# 2_classyTKL_matrix.net
KiCad netlist of a schematic drawn in Altium Designer
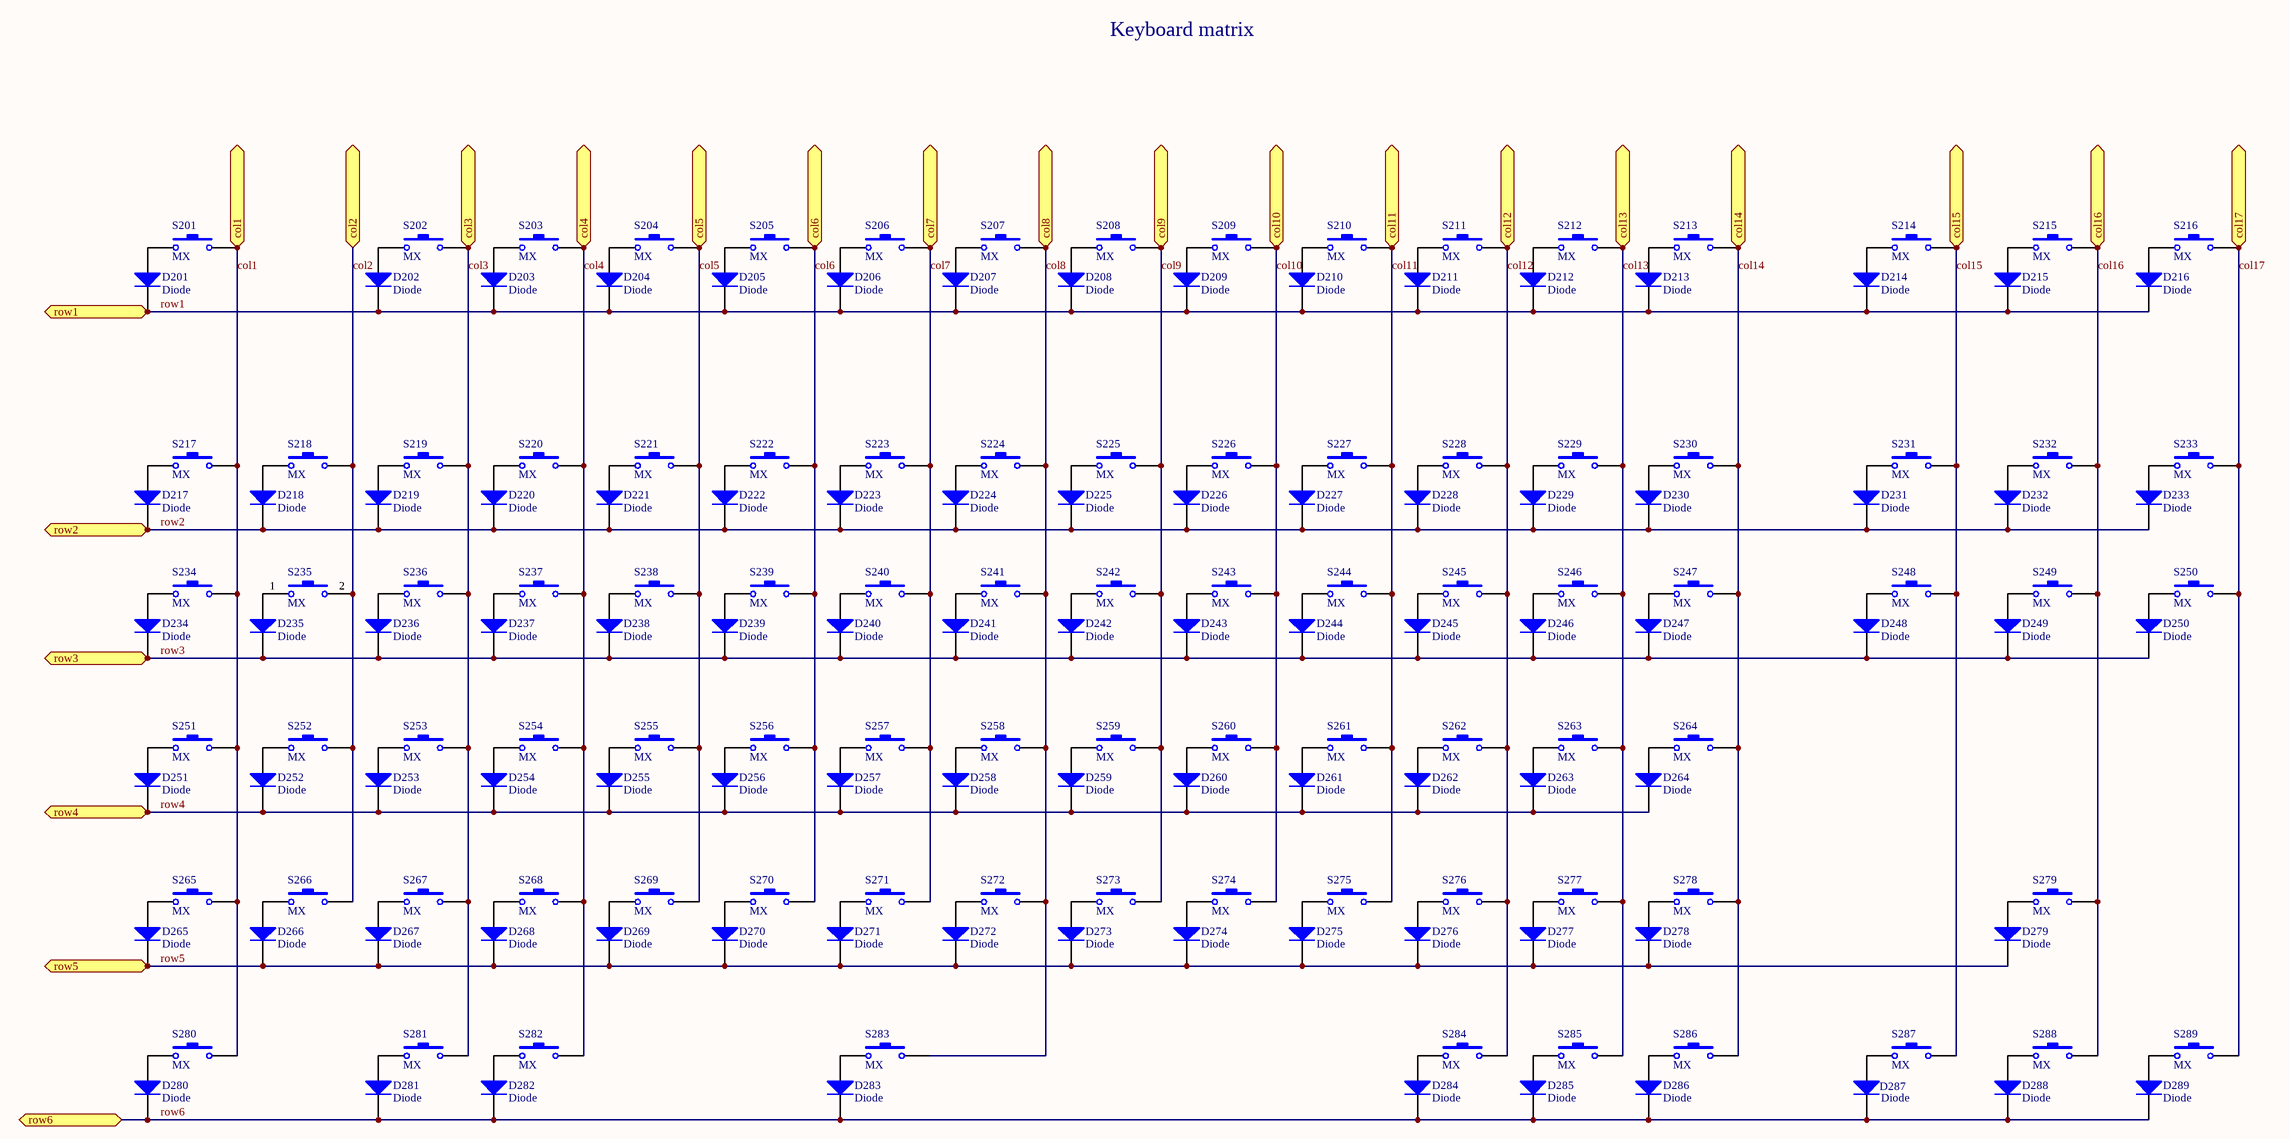
[diagram p0: 2_classyTKL_matrix.SchDoc]

(export (version "E")
  (design (tool "Eeschema 10.0.6"))
  (components
    (comp (ref "D201")
      (value "Diode")
      (footprint "D0603[1608]")
      (description "Default Diode")
      (fields (field (name "MFG") "Bourns Inc.") (field (name "LCSC PART #") "C109002"))
      (libsource (lib "Miscellaneous Devices") (part "Diode"))
    )
    (comp (ref "D202")
      (value "Diode")
      (footprint "D0603[1608]")
      (description "Default Diode")
      (fields (field (name "MFG") "Bourns Inc.") (field (name "LCSC PART #") "C109002"))
      (libsource (lib "Miscellaneous Devices") (part "Diode"))
    )
    (comp (ref "D203")
      (value "Diode")
      (footprint "D0603[1608]")
      (description "Default Diode")
      (fields (field (name "MFG") "Bourns Inc.") (field (name "LCSC PART #") "C109002"))
      (libsource (lib "Miscellaneous Devices") (part "Diode"))
    )
    (comp (ref "D204")
      (value "Diode")
      (footprint "D0603[1608]")
      (description "Default Diode")
      (fields (field (name "MFG") "Bourns Inc.") (field (name "LCSC PART #") "C109002"))
      (libsource (lib "Miscellaneous Devices") (part "Diode"))
    )
    (comp (ref "D205")
      (value "Diode")
      (footprint "D0603[1608]")
      (description "Default Diode")
      (fields (field (name "MFG") "Bourns Inc.") (field (name "LCSC PART #") "C109002"))
      (libsource (lib "Miscellaneous Devices") (part "Diode"))
    )
    (comp (ref "D206")
      (value "Diode")
      (footprint "D0603[1608]")
      (description "Default Diode")
      (fields (field (name "MFG") "Bourns Inc.") (field (name "LCSC PART #") "C109002"))
      (libsource (lib "Miscellaneous Devices") (part "Diode"))
    )
    (comp (ref "D207")
      (value "Diode")
      (footprint "D0603[1608]")
      (description "Default Diode")
      (fields (field (name "MFG") "Bourns Inc.") (field (name "LCSC PART #") "C109002"))
      (libsource (lib "Miscellaneous Devices") (part "Diode"))
    )
    (comp (ref "D208")
      (value "Diode")
      (footprint "D0603[1608]")
      (description "Default Diode")
      (fields (field (name "MFG") "Bourns Inc.") (field (name "LCSC PART #") "C109002"))
      (libsource (lib "Miscellaneous Devices") (part "Diode"))
    )
    (comp (ref "D209")
      (value "Diode")
      (footprint "D0603[1608]")
      (description "Default Diode")
      (fields (field (name "MFG") "Bourns Inc.") (field (name "LCSC PART #") "C109002"))
      (libsource (lib "Miscellaneous Devices") (part "Diode"))
    )
    (comp (ref "D210")
      (value "Diode")
      (footprint "D0603[1608]")
      (description "Default Diode")
      (fields (field (name "MFG") "Bourns Inc.") (field (name "LCSC PART #") "C109002"))
      (libsource (lib "Miscellaneous Devices") (part "Diode"))
    )
    (comp (ref "D211")
      (value "Diode")
      (footprint "D0603[1608]")
      (description "Default Diode")
      (fields (field (name "MFG") "Bourns Inc.") (field (name "LCSC PART #") "C109002"))
      (libsource (lib "Miscellaneous Devices") (part "Diode"))
    )
    (comp (ref "D212")
      (value "Diode")
      (footprint "D0603[1608]")
      (description "Default Diode")
      (fields (field (name "MFG") "Bourns Inc.") (field (name "LCSC PART #") "C109002"))
      (libsource (lib "Miscellaneous Devices") (part "Diode"))
    )
    (comp (ref "D213")
      (value "Diode")
      (footprint "D0603[1608]")
      (description "Default Diode")
      (fields (field (name "MFG") "Bourns Inc.") (field (name "LCSC PART #") "C109002"))
      (libsource (lib "Miscellaneous Devices") (part "Diode"))
    )
    (comp (ref "D214")
      (value "Diode")
      (footprint "D0603[1608]")
      (description "Default Diode")
      (fields (field (name "MFG") "Bourns Inc.") (field (name "LCSC PART #") "C109002"))
      (libsource (lib "Miscellaneous Devices") (part "Diode"))
    )
    (comp (ref "D215")
      (value "Diode")
      (footprint "D0603[1608]")
      (description "Default Diode")
      (fields (field (name "MFG") "Bourns Inc.") (field (name "LCSC PART #") "C109002"))
      (libsource (lib "Miscellaneous Devices") (part "Diode"))
    )
    (comp (ref "D216")
      (value "Diode")
      (footprint "D0603[1608]")
      (description "Default Diode")
      (fields (field (name "MFG") "Bourns Inc.") (field (name "LCSC PART #") "C109002"))
      (libsource (lib "Miscellaneous Devices") (part "Diode"))
    )
    (comp (ref "D217")
      (value "Diode")
      (footprint "D0603[1608]")
      (description "Default Diode")
      (fields (field (name "MFG") "Bourns Inc.") (field (name "LCSC PART #") "C109002"))
      (libsource (lib "Miscellaneous Devices") (part "Diode"))
    )
    (comp (ref "D218")
      (value "Diode")
      (footprint "D0603[1608]")
      (description "Default Diode")
      (fields (field (name "MFG") "Bourns Inc.") (field (name "LCSC PART #") "C109002"))
      (libsource (lib "Miscellaneous Devices") (part "Diode"))
    )
    (comp (ref "D219")
      (value "Diode")
      (footprint "D0603[1608]")
      (description "Default Diode")
      (fields (field (name "MFG") "Bourns Inc.") (field (name "LCSC PART #") "C109002"))
      (libsource (lib "Miscellaneous Devices") (part "Diode"))
    )
    (comp (ref "D220")
      (value "Diode")
      (footprint "D0603[1608]")
      (description "Default Diode")
      (fields (field (name "MFG") "Bourns Inc.") (field (name "LCSC PART #") "C109002"))
      (libsource (lib "Miscellaneous Devices") (part "Diode"))
    )
    (comp (ref "D221")
      (value "Diode")
      (footprint "D0603[1608]")
      (description "Default Diode")
      (fields (field (name "MFG") "Bourns Inc.") (field (name "LCSC PART #") "C109002"))
      (libsource (lib "Miscellaneous Devices") (part "Diode"))
    )
    (comp (ref "D222")
      (value "Diode")
      (footprint "D0603[1608]")
      (description "Default Diode")
      (fields (field (name "MFG") "Bourns Inc.") (field (name "LCSC PART #") "C109002"))
      (libsource (lib "Miscellaneous Devices") (part "Diode"))
    )
    (comp (ref "D223")
      (value "Diode")
      (footprint "D0603[1608]")
      (description "Default Diode")
      (fields (field (name "MFG") "Bourns Inc.") (field (name "LCSC PART #") "C109002"))
      (libsource (lib "Miscellaneous Devices") (part "Diode"))
    )
    (comp (ref "D224")
      (value "Diode")
      (footprint "D0603[1608]")
      (description "Default Diode")
      (fields (field (name "MFG") "Bourns Inc.") (field (name "LCSC PART #") "C109002"))
      (libsource (lib "Miscellaneous Devices") (part "Diode"))
    )
    (comp (ref "D225")
      (value "Diode")
      (footprint "D0603[1608]")
      (description "Default Diode")
      (fields (field (name "MFG") "Bourns Inc.") (field (name "LCSC PART #") "C109002"))
      (libsource (lib "Miscellaneous Devices") (part "Diode"))
    )
    (comp (ref "D226")
      (value "Diode")
      (footprint "D0603[1608]")
      (description "Default Diode")
      (fields (field (name "MFG") "Bourns Inc.") (field (name "LCSC PART #") "C109002"))
      (libsource (lib "Miscellaneous Devices") (part "Diode"))
    )
    (comp (ref "D227")
      (value "Diode")
      (footprint "D0603[1608]")
      (description "Default Diode")
      (fields (field (name "MFG") "Bourns Inc.") (field (name "LCSC PART #") "C109002"))
      (libsource (lib "Miscellaneous Devices") (part "Diode"))
    )
    (comp (ref "D228")
      (value "Diode")
      (footprint "D0603[1608]")
      (description "Default Diode")
      (fields (field (name "MFG") "Bourns Inc.") (field (name "LCSC PART #") "C109002"))
      (libsource (lib "Miscellaneous Devices") (part "Diode"))
    )
    (comp (ref "D229")
      (value "Diode")
      (footprint "D0603[1608]")
      (description "Default Diode")
      (fields (field (name "MFG") "Bourns Inc.") (field (name "LCSC PART #") "C109002"))
      (libsource (lib "Miscellaneous Devices") (part "Diode"))
    )
    (comp (ref "D230")
      (value "Diode")
      (footprint "D0603[1608]")
      (description "Default Diode")
      (fields (field (name "MFG") "Bourns Inc.") (field (name "LCSC PART #") "C109002"))
      (libsource (lib "Miscellaneous Devices") (part "Diode"))
    )
    (comp (ref "D231")
      (value "Diode")
      (footprint "D0603[1608]")
      (description "Default Diode")
      (fields (field (name "MFG") "Bourns Inc.") (field (name "LCSC PART #") "C109002"))
      (libsource (lib "Miscellaneous Devices") (part "Diode"))
    )
    (comp (ref "D232")
      (value "Diode")
      (footprint "D0603[1608]")
      (description "Default Diode")
      (fields (field (name "MFG") "Bourns Inc.") (field (name "LCSC PART #") "C109002"))
      (libsource (lib "Miscellaneous Devices") (part "Diode"))
    )
    (comp (ref "D233")
      (value "Diode")
      (footprint "D0603[1608]")
      (description "Default Diode")
      (fields (field (name "MFG") "Bourns Inc.") (field (name "LCSC PART #") "C109002"))
      (libsource (lib "Miscellaneous Devices") (part "Diode"))
    )
    (comp (ref "D234")
      (value "Diode")
      (footprint "D0603[1608]")
      (description "Default Diode")
      (fields (field (name "MFG") "Bourns Inc.") (field (name "LCSC PART #") "C109002"))
      (libsource (lib "Miscellaneous Devices") (part "Diode"))
    )
    (comp (ref "D235")
      (value "Diode")
      (footprint "D0603[1608]")
      (description "Default Diode")
      (fields (field (name "MFG") "Bourns Inc.") (field (name "LCSC PART #") "C109002"))
      (libsource (lib "Miscellaneous Devices") (part "Diode"))
    )
    (comp (ref "D236")
      (value "Diode")
      (footprint "D0603[1608]")
      (description "Default Diode")
      (fields (field (name "MFG") "Bourns Inc.") (field (name "LCSC PART #") "C109002"))
      (libsource (lib "Miscellaneous Devices") (part "Diode"))
    )
    (comp (ref "D237")
      (value "Diode")
      (footprint "D0603[1608]")
      (description "Default Diode")
      (fields (field (name "MFG") "Bourns Inc.") (field (name "LCSC PART #") "C109002"))
      (libsource (lib "Miscellaneous Devices") (part "Diode"))
    )
    (comp (ref "D238")
      (value "Diode")
      (footprint "D0603[1608]")
      (description "Default Diode")
      (fields (field (name "MFG") "Bourns Inc.") (field (name "LCSC PART #") "C109002"))
      (libsource (lib "Miscellaneous Devices") (part "Diode"))
    )
    (comp (ref "D239")
      (value "Diode")
      (footprint "D0603[1608]")
      (description "Default Diode")
      (fields (field (name "MFG") "Bourns Inc.") (field (name "LCSC PART #") "C109002"))
      (libsource (lib "Miscellaneous Devices") (part "Diode"))
    )
    (comp (ref "D240")
      (value "Diode")
      (footprint "D0603[1608]")
      (description "Default Diode")
      (fields (field (name "MFG") "Bourns Inc.") (field (name "LCSC PART #") "C109002"))
      (libsource (lib "Miscellaneous Devices") (part "Diode"))
    )
    (comp (ref "D241")
      (value "Diode")
      (footprint "D0603[1608]")
      (description "Default Diode")
      (fields (field (name "MFG") "Bourns Inc.") (field (name "LCSC PART #") "C109002"))
      (libsource (lib "Miscellaneous Devices") (part "Diode"))
    )
    (comp (ref "D242")
      (value "Diode")
      (footprint "D0603[1608]")
      (description "Default Diode")
      (fields (field (name "MFG") "Bourns Inc.") (field (name "LCSC PART #") "C109002"))
      (libsource (lib "Miscellaneous Devices") (part "Diode"))
    )
    (comp (ref "D243")
      (value "Diode")
      (footprint "D0603[1608]")
      (description "Default Diode")
      (fields (field (name "MFG") "Bourns Inc.") (field (name "LCSC PART #") "C109002"))
      (libsource (lib "Miscellaneous Devices") (part "Diode"))
    )
    (comp (ref "D244")
      (value "Diode")
      (footprint "D0603[1608]")
      (description "Default Diode")
      (fields (field (name "MFG") "Bourns Inc.") (field (name "LCSC PART #") "C109002"))
      (libsource (lib "Miscellaneous Devices") (part "Diode"))
    )
    (comp (ref "D245")
      (value "Diode")
      (footprint "D0603[1608]")
      (description "Default Diode")
      (fields (field (name "MFG") "Bourns Inc.") (field (name "LCSC PART #") "C109002"))
      (libsource (lib "Miscellaneous Devices") (part "Diode"))
    )
    (comp (ref "D246")
      (value "Diode")
      (footprint "D0603[1608]")
      (description "Default Diode")
      (fields (field (name "MFG") "Bourns Inc.") (field (name "LCSC PART #") "C109002"))
      (libsource (lib "Miscellaneous Devices") (part "Diode"))
    )
    (comp (ref "D247")
      (value "Diode")
      (footprint "D0603[1608]")
      (description "Default Diode")
      (fields (field (name "MFG") "Bourns Inc.") (field (name "LCSC PART #") "C109002"))
      (libsource (lib "Miscellaneous Devices") (part "Diode"))
    )
    (comp (ref "D248")
      (value "Diode")
      (footprint "D0603[1608]")
      (description "Default Diode")
      (fields (field (name "MFG") "Bourns Inc.") (field (name "LCSC PART #") "C109002"))
      (libsource (lib "Miscellaneous Devices") (part "Diode"))
    )
    (comp (ref "D249")
      (value "Diode")
      (footprint "D0603[1608]")
      (description "Default Diode")
      (fields (field (name "MFG") "Bourns Inc.") (field (name "LCSC PART #") "C109002"))
      (libsource (lib "Miscellaneous Devices") (part "Diode"))
    )
    (comp (ref "D250")
      (value "Diode")
      (footprint "D0603[1608]")
      (description "Default Diode")
      (fields (field (name "MFG") "Bourns Inc.") (field (name "LCSC PART #") "C109002"))
      (libsource (lib "Miscellaneous Devices") (part "Diode"))
    )
    (comp (ref "D251")
      (value "Diode")
      (footprint "D0603[1608]")
      (description "Default Diode")
      (fields (field (name "MFG") "Bourns Inc.") (field (name "LCSC PART #") "C109002"))
      (libsource (lib "Miscellaneous Devices") (part "Diode"))
    )
    (comp (ref "D252")
      (value "Diode")
      (footprint "D0603[1608]")
      (description "Default Diode")
      (fields (field (name "MFG") "Bourns Inc.") (field (name "LCSC PART #") "C109002"))
      (libsource (lib "Miscellaneous Devices") (part "Diode"))
    )
    (comp (ref "D253")
      (value "Diode")
      (footprint "D0603[1608]")
      (description "Default Diode")
      (fields (field (name "MFG") "Bourns Inc.") (field (name "LCSC PART #") "C109002"))
      (libsource (lib "Miscellaneous Devices") (part "Diode"))
    )
    (comp (ref "D254")
      (value "Diode")
      (footprint "D0603[1608]")
      (description "Default Diode")
      (fields (field (name "MFG") "Bourns Inc.") (field (name "LCSC PART #") "C109002"))
      (libsource (lib "Miscellaneous Devices") (part "Diode"))
    )
    (comp (ref "D255")
      (value "Diode")
      (footprint "D0603[1608]")
      (description "Default Diode")
      (fields (field (name "MFG") "Bourns Inc.") (field (name "LCSC PART #") "C109002"))
      (libsource (lib "Miscellaneous Devices") (part "Diode"))
    )
    (comp (ref "D256")
      (value "Diode")
      (footprint "D0603[1608]")
      (description "Default Diode")
      (fields (field (name "MFG") "Bourns Inc.") (field (name "LCSC PART #") "C109002"))
      (libsource (lib "Miscellaneous Devices") (part "Diode"))
    )
    (comp (ref "D257")
      (value "Diode")
      (footprint "D0603[1608]")
      (description "Default Diode")
      (fields (field (name "MFG") "Bourns Inc.") (field (name "LCSC PART #") "C109002"))
      (libsource (lib "Miscellaneous Devices") (part "Diode"))
    )
    (comp (ref "D258")
      (value "Diode")
      (footprint "D0603[1608]")
      (description "Default Diode")
      (fields (field (name "MFG") "Bourns Inc.") (field (name "LCSC PART #") "C109002"))
      (libsource (lib "Miscellaneous Devices") (part "Diode"))
    )
    (comp (ref "D259")
      (value "Diode")
      (footprint "D0603[1608]")
      (description "Default Diode")
      (fields (field (name "MFG") "Bourns Inc.") (field (name "LCSC PART #") "C109002"))
      (libsource (lib "Miscellaneous Devices") (part "Diode"))
    )
    (comp (ref "D260")
      (value "Diode")
      (footprint "D0603[1608]")
      (description "Default Diode")
      (fields (field (name "MFG") "Bourns Inc.") (field (name "LCSC PART #") "C109002"))
      (libsource (lib "Miscellaneous Devices") (part "Diode"))
    )
    (comp (ref "D261")
      (value "Diode")
      (footprint "D0603[1608]")
      (description "Default Diode")
      (fields (field (name "MFG") "Bourns Inc.") (field (name "LCSC PART #") "C109002"))
      (libsource (lib "Miscellaneous Devices") (part "Diode"))
    )
    (comp (ref "D262")
      (value "Diode")
      (footprint "D0603[1608]")
      (description "Default Diode")
      (fields (field (name "MFG") "Bourns Inc.") (field (name "LCSC PART #") "C109002"))
      (libsource (lib "Miscellaneous Devices") (part "Diode"))
    )
    (comp (ref "D263")
      (value "Diode")
      (footprint "D0603[1608]")
      (description "Default Diode")
      (fields (field (name "MFG") "Bourns Inc.") (field (name "LCSC PART #") "C109002"))
      (libsource (lib "Miscellaneous Devices") (part "Diode"))
    )
    (comp (ref "D264")
      (value "Diode")
      (footprint "D0603[1608]")
      (description "Default Diode")
      (fields (field (name "MFG") "Bourns Inc.") (field (name "LCSC PART #") "C109002"))
      (libsource (lib "Miscellaneous Devices") (part "Diode"))
    )
    (comp (ref "D265")
      (value "Diode")
      (footprint "D0603[1608]")
      (description "Default Diode")
      (fields (field (name "MFG") "Bourns Inc.") (field (name "LCSC PART #") "C109002"))
      (libsource (lib "Miscellaneous Devices") (part "Diode"))
    )
    (comp (ref "D266")
      (value "Diode")
      (footprint "D0603[1608]")
      (description "Default Diode")
      (fields (field (name "MFG") "Bourns Inc.") (field (name "LCSC PART #") "C109002"))
      (libsource (lib "Miscellaneous Devices") (part "Diode"))
    )
    (comp (ref "D267")
      (value "Diode")
      (footprint "D0603[1608]")
      (description "Default Diode")
      (fields (field (name "MFG") "Bourns Inc.") (field (name "LCSC PART #") "C109002"))
      (libsource (lib "Miscellaneous Devices") (part "Diode"))
    )
    (comp (ref "D268")
      (value "Diode")
      (footprint "D0603[1608]")
      (description "Default Diode")
      (fields (field (name "MFG") "Bourns Inc.") (field (name "LCSC PART #") "C109002"))
      (libsource (lib "Miscellaneous Devices") (part "Diode"))
    )
    (comp (ref "D269")
      (value "Diode")
      (footprint "D0603[1608]")
      (description "Default Diode")
      (fields (field (name "MFG") "Bourns Inc.") (field (name "LCSC PART #") "C109002"))
      (libsource (lib "Miscellaneous Devices") (part "Diode"))
    )
    (comp (ref "D270")
      (value "Diode")
      (footprint "D0603[1608]")
      (description "Default Diode")
      (fields (field (name "MFG") "Bourns Inc.") (field (name "LCSC PART #") "C109002"))
      (libsource (lib "Miscellaneous Devices") (part "Diode"))
    )
    (comp (ref "D271")
      (value "Diode")
      (footprint "D0603[1608]")
      (description "Default Diode")
      (fields (field (name "MFG") "Bourns Inc.") (field (name "LCSC PART #") "C109002"))
      (libsource (lib "Miscellaneous Devices") (part "Diode"))
    )
    (comp (ref "D272")
      (value "Diode")
      (footprint "D0603[1608]")
      (description "Default Diode")
      (fields (field (name "MFG") "Bourns Inc.") (field (name "LCSC PART #") "C109002"))
      (libsource (lib "Miscellaneous Devices") (part "Diode"))
    )
    (comp (ref "D273")
      (value "Diode")
      (footprint "D0603[1608]")
      (description "Default Diode")
      (fields (field (name "MFG") "Bourns Inc.") (field (name "LCSC PART #") "C109002"))
      (libsource (lib "Miscellaneous Devices") (part "Diode"))
    )
    (comp (ref "D274")
      (value "Diode")
      (footprint "D0603[1608]")
      (description "Default Diode")
      (fields (field (name "MFG") "Bourns Inc.") (field (name "LCSC PART #") "C109002"))
      (libsource (lib "Miscellaneous Devices") (part "Diode"))
    )
    (comp (ref "D275")
      (value "Diode")
      (footprint "D0603[1608]")
      (description "Default Diode")
      (fields (field (name "MFG") "Bourns Inc.") (field (name "LCSC PART #") "C109002"))
      (libsource (lib "Miscellaneous Devices") (part "Diode"))
    )
    (comp (ref "D276")
      (value "Diode")
      (footprint "D0603[1608]")
      (description "Default Diode")
      (fields (field (name "MFG") "Bourns Inc.") (field (name "LCSC PART #") "C109002"))
      (libsource (lib "Miscellaneous Devices") (part "Diode"))
    )
    (comp (ref "D277")
      (value "Diode")
      (footprint "D0603[1608]")
      (description "Default Diode")
      (fields (field (name "MFG") "Bourns Inc.") (field (name "LCSC PART #") "C109002"))
      (libsource (lib "Miscellaneous Devices") (part "Diode"))
    )
    (comp (ref "D278")
      (value "Diode")
      (footprint "D0603[1608]")
      (description "Default Diode")
      (fields (field (name "MFG") "Bourns Inc.") (field (name "LCSC PART #") "C109002"))
      (libsource (lib "Miscellaneous Devices") (part "Diode"))
    )
    (comp (ref "D279")
      (value "Diode")
      (footprint "D0603[1608]")
      (description "Default Diode")
      (fields (field (name "MFG") "Bourns Inc.") (field (name "LCSC PART #") "C109002"))
      (libsource (lib "Miscellaneous Devices") (part "Diode"))
    )
    (comp (ref "D280")
      (value "Diode")
      (footprint "D0603[1608]")
      (description "Default Diode")
      (fields (field (name "MFG") "Bourns Inc.") (field (name "LCSC PART #") "C109002"))
      (libsource (lib "Miscellaneous Devices") (part "Diode"))
    )
    (comp (ref "D281")
      (value "Diode")
      (footprint "D0603[1608]")
      (description "Default Diode")
      (fields (field (name "MFG") "Bourns Inc.") (field (name "LCSC PART #") "C109002"))
      (libsource (lib "Miscellaneous Devices") (part "Diode"))
    )
    (comp (ref "D282")
      (value "Diode")
      (footprint "D0603[1608]")
      (description "Default Diode")
      (fields (field (name "MFG") "Bourns Inc.") (field (name "LCSC PART #") "C109002"))
      (libsource (lib "Miscellaneous Devices") (part "Diode"))
    )
    (comp (ref "D283")
      (value "Diode")
      (footprint "D0603[1608]")
      (description "Default Diode")
      (fields (field (name "MFG") "Bourns Inc.") (field (name "LCSC PART #") "C109002"))
      (libsource (lib "Miscellaneous Devices") (part "Diode"))
    )
    (comp (ref "D284")
      (value "Diode")
      (footprint "D0603[1608]")
      (description "Default Diode")
      (fields (field (name "MFG") "Bourns Inc.") (field (name "LCSC PART #") "C109002"))
      (libsource (lib "Miscellaneous Devices") (part "Diode"))
    )
    (comp (ref "D285")
      (value "Diode")
      (footprint "D0603[1608]")
      (description "Default Diode")
      (fields (field (name "MFG") "Bourns Inc.") (field (name "LCSC PART #") "C109002"))
      (libsource (lib "Miscellaneous Devices") (part "Diode"))
    )
    (comp (ref "D286")
      (value "Diode")
      (footprint "D0603[1608]")
      (description "Default Diode")
      (fields (field (name "MFG") "Bourns Inc.") (field (name "LCSC PART #") "C109002"))
      (libsource (lib "Miscellaneous Devices") (part "Diode"))
    )
    (comp (ref "D287")
      (value "Diode")
      (footprint "D0603[1608]")
      (description "Default Diode")
      (fields (field (name "MFG") "Bourns Inc.") (field (name "LCSC PART #") "C109002"))
      (libsource (lib "Miscellaneous Devices") (part "Diode"))
    )
    (comp (ref "D288")
      (value "Diode")
      (footprint "D0603[1608]")
      (description "Default Diode")
      (fields (field (name "MFG") "Bourns Inc.") (field (name "LCSC PART #") "C109002"))
      (libsource (lib "Miscellaneous Devices") (part "Diode"))
    )
    (comp (ref "D289")
      (value "Diode")
      (footprint "D0603[1608]")
      (description "Default Diode")
      (fields (field (name "MFG") "Bourns Inc.") (field (name "LCSC PART #") "C109002"))
      (libsource (lib "Miscellaneous Devices") (part "Diode"))
    )
    (comp (ref "S201")
      (value "MX")
      (footprint "MX-switch - switched pol")
      (description "Switch")
      (libsource (lib "Miscellaneous Devices") (part "SW-PB"))
    )
    (comp (ref "S202")
      (value "MX")
      (footprint "MX-switch")
      (description "Switch")
      (libsource (lib "Miscellaneous Devices") (part "SW-PB"))
    )
    (comp (ref "S203")
      (value "MX")
      (footprint "MX-switch")
      (description "Switch")
      (libsource (lib "Miscellaneous Devices") (part "SW-PB"))
    )
    (comp (ref "S204")
      (value "MX")
      (footprint "MX-switch")
      (description "Switch")
      (libsource (lib "Miscellaneous Devices") (part "SW-PB"))
    )
    (comp (ref "S205")
      (value "MX")
      (footprint "MX-switch")
      (description "Switch")
      (libsource (lib "Miscellaneous Devices") (part "SW-PB"))
    )
    (comp (ref "S206")
      (value "MX")
      (footprint "MX-switch")
      (description "Switch")
      (libsource (lib "Miscellaneous Devices") (part "SW-PB"))
    )
    (comp (ref "S207")
      (value "MX")
      (footprint "MX-switch")
      (description "Switch")
      (libsource (lib "Miscellaneous Devices") (part "SW-PB"))
    )
    (comp (ref "S208")
      (value "MX")
      (footprint "MX-switch")
      (description "Switch")
      (libsource (lib "Miscellaneous Devices") (part "SW-PB"))
    )
    (comp (ref "S209")
      (value "MX")
      (footprint "MX-switch")
      (description "Switch")
      (libsource (lib "Miscellaneous Devices") (part "SW-PB"))
    )
    (comp (ref "S210")
      (value "MX")
      (footprint "MX-switch")
      (description "Switch")
      (libsource (lib "Miscellaneous Devices") (part "SW-PB"))
    )
    (comp (ref "S211")
      (value "MX")
      (footprint "MX-switch")
      (description "Switch")
      (libsource (lib "Miscellaneous Devices") (part "SW-PB"))
    )
    (comp (ref "S212")
      (value "MX")
      (footprint "MX-switch")
      (description "Switch")
      (libsource (lib "Miscellaneous Devices") (part "SW-PB"))
    )
    (comp (ref "S213")
      (value "MX")
      (footprint "MX-switch")
      (description "Switch")
      (libsource (lib "Miscellaneous Devices") (part "SW-PB"))
    )
    (comp (ref "S214")
      (value "MX")
      (footprint "MX-switch")
      (description "Switch")
      (libsource (lib "Miscellaneous Devices") (part "SW-PB"))
    )
    (comp (ref "S215")
      (value "MX")
      (footprint "MX-switch")
      (description "Switch")
      (libsource (lib "Miscellaneous Devices") (part "SW-PB"))
    )
    (comp (ref "S216")
      (value "MX")
      (footprint "MX-switch")
      (description "Switch")
      (libsource (lib "Miscellaneous Devices") (part "SW-PB"))
    )
    (comp (ref "S217")
      (value "MX")
      (footprint "MX-switch - switched pol")
      (description "Switch")
      (libsource (lib "Miscellaneous Devices") (part "SW-PB"))
    )
    (comp (ref "S218")
      (value "MX")
      (footprint "MX-switch - switched pol")
      (description "Switch")
      (libsource (lib "Miscellaneous Devices") (part "SW-PB"))
    )
    (comp (ref "S219")
      (value "MX")
      (footprint "MX-switch - switched pol")
      (description "Switch")
      (libsource (lib "Miscellaneous Devices") (part "SW-PB"))
    )
    (comp (ref "S220")
      (value "MX")
      (footprint "MX-switch - switched pol")
      (description "Switch")
      (libsource (lib "Miscellaneous Devices") (part "SW-PB"))
    )
    (comp (ref "S221")
      (value "MX")
      (footprint "MX-switch - switched pol")
      (description "Switch")
      (libsource (lib "Miscellaneous Devices") (part "SW-PB"))
    )
    (comp (ref "S222")
      (value "MX")
      (footprint "MX-switch - switched pol")
      (description "Switch")
      (libsource (lib "Miscellaneous Devices") (part "SW-PB"))
    )
    (comp (ref "S223")
      (value "MX")
      (footprint "MX-switch - switched pol")
      (description "Switch")
      (libsource (lib "Miscellaneous Devices") (part "SW-PB"))
    )
    (comp (ref "S224")
      (value "MX")
      (footprint "MX-switch - switched pol")
      (description "Switch")
      (libsource (lib "Miscellaneous Devices") (part "SW-PB"))
    )
    (comp (ref "S225")
      (value "MX")
      (footprint "MX-switch - switched pol")
      (description "Switch")
      (libsource (lib "Miscellaneous Devices") (part "SW-PB"))
    )
    (comp (ref "S226")
      (value "MX")
      (footprint "MX-switch - switched pol")
      (description "Switch")
      (libsource (lib "Miscellaneous Devices") (part "SW-PB"))
    )
    (comp (ref "S227")
      (value "MX")
      (footprint "MX-switch - switched pol")
      (description "Switch")
      (libsource (lib "Miscellaneous Devices") (part "SW-PB"))
    )
    (comp (ref "S228")
      (value "MX")
      (footprint "MX-switch - switched pol")
      (description "Switch")
      (libsource (lib "Miscellaneous Devices") (part "SW-PB"))
    )
    (comp (ref "S229")
      (value "MX")
      (footprint "MX-switch - switched pol")
      (description "Switch")
      (libsource (lib "Miscellaneous Devices") (part "SW-PB"))
    )
    (comp (ref "S230")
      (value "MX")
      (footprint "MX-switch")
      (description "Switch")
      (libsource (lib "Miscellaneous Devices") (part "SW-PB"))
    )
    (comp (ref "S231")
      (value "MX")
      (footprint "MX-switch")
      (description "Switch")
      (libsource (lib "Miscellaneous Devices") (part "SW-PB"))
    )
    (comp (ref "S232")
      (value "MX")
      (footprint "MX-switch")
      (description "Switch")
      (libsource (lib "Miscellaneous Devices") (part "SW-PB"))
    )
    (comp (ref "S233")
      (value "MX")
      (footprint "MX-switch")
      (description "Switch")
      (libsource (lib "Miscellaneous Devices") (part "SW-PB"))
    )
    (comp (ref "S234")
      (value "MX")
      (footprint "MX-switch - 1.5U - switched pol")
      (description "TAB")
      (libsource (lib "Miscellaneous Devices") (part "SW-PB"))
    )
    (comp (ref "S235")
      (value "MX")
      (footprint "MX-switch - switched pol")
      (description "Switch")
      (libsource (lib "") (part "SW-PB_1"))
    )
    (comp (ref "S236")
      (value "MX")
      (footprint "MX-switch - switched pol")
      (description "Switch")
      (libsource (lib "Miscellaneous Devices") (part "SW-PB"))
    )
    (comp (ref "S237")
      (value "MX")
      (footprint "MX-switch - switched pol")
      (description "Switch")
      (libsource (lib "Miscellaneous Devices") (part "SW-PB"))
    )
    (comp (ref "S238")
      (value "MX")
      (footprint "MX-switch - switched pol")
      (description "Switch")
      (libsource (lib "Miscellaneous Devices") (part "SW-PB"))
    )
    (comp (ref "S239")
      (value "MX")
      (footprint "MX-switch - switched pol")
      (description "Switch")
      (libsource (lib "Miscellaneous Devices") (part "SW-PB"))
    )
    (comp (ref "S240")
      (value "MX")
      (footprint "MX-switch - switched pol")
      (description "Switch")
      (libsource (lib "Miscellaneous Devices") (part "SW-PB"))
    )
    (comp (ref "S241")
      (value "MX")
      (footprint "MX-switch - switched pol")
      (description "Switch")
      (libsource (lib "Miscellaneous Devices") (part "SW-PB"))
    )
    (comp (ref "S242")
      (value "MX")
      (footprint "MX-switch - switched pol")
      (description "Switch")
      (libsource (lib "Miscellaneous Devices") (part "SW-PB"))
    )
    (comp (ref "S243")
      (value "MX")
      (footprint "MX-switch - switched pol")
      (description "Switch")
      (libsource (lib "Miscellaneous Devices") (part "SW-PB"))
    )
    (comp (ref "S244")
      (value "MX")
      (footprint "MX-switch - switched pol")
      (description "Switch")
      (libsource (lib "Miscellaneous Devices") (part "SW-PB"))
    )
    (comp (ref "S245")
      (value "MX")
      (footprint "MX-switch - switched pol")
      (description "Switch")
      (libsource (lib "Miscellaneous Devices") (part "SW-PB"))
    )
    (comp (ref "S246")
      (value "MX")
      (footprint "MX-switch - switched pol")
      (description "Switch")
      (libsource (lib "Miscellaneous Devices") (part "SW-PB"))
    )
    (comp (ref "S247")
      (value "MX")
      (footprint "MX-switch - PIPE_ISO_ENTER")
      (description "Switch")
      (libsource (lib "Miscellaneous Devices") (part "SW-PB"))
    )
    (comp (ref "S248")
      (value "MX")
      (footprint "MX-switch")
      (description "Switch")
      (libsource (lib "Miscellaneous Devices") (part "SW-PB"))
    )
    (comp (ref "S249")
      (value "MX")
      (footprint "MX-switch")
      (description "Switch")
      (libsource (lib "Miscellaneous Devices") (part "SW-PB"))
    )
    (comp (ref "S250")
      (value "MX")
      (footprint "MX-switch")
      (description "Switch")
      (libsource (lib "Miscellaneous Devices") (part "SW-PB"))
    )
    (comp (ref "S251")
      (value "MX")
      (footprint "MX-switch - CAPS")
      (description "Switch")
      (libsource (lib "Miscellaneous Devices") (part "SW-PB"))
    )
    (comp (ref "S252")
      (value "MX")
      (footprint "MX-switch - switched pol")
      (description "Switch")
      (libsource (lib "Miscellaneous Devices") (part "SW-PB"))
    )
    (comp (ref "S253")
      (value "MX")
      (footprint "MX-switch - switched pol")
      (description "Switch")
      (libsource (lib "Miscellaneous Devices") (part "SW-PB"))
    )
    (comp (ref "S254")
      (value "MX")
      (footprint "MX-switch - switched pol")
      (description "Switch")
      (libsource (lib "Miscellaneous Devices") (part "SW-PB"))
    )
    (comp (ref "S255")
      (value "MX")
      (footprint "MX-switch - switched pol")
      (description "Switch")
      (libsource (lib "Miscellaneous Devices") (part "SW-PB"))
    )
    (comp (ref "S256")
      (value "MX")
      (footprint "MX-switch - switched pol")
      (description "Switch")
      (libsource (lib "Miscellaneous Devices") (part "SW-PB"))
    )
    (comp (ref "S257")
      (value "MX")
      (footprint "MX-switch - switched pol")
      (description "Switch")
      (libsource (lib "Miscellaneous Devices") (part "SW-PB"))
    )
    (comp (ref "S258")
      (value "MX")
      (footprint "MX-switch - switched pol")
      (description "Switch")
      (libsource (lib "Miscellaneous Devices") (part "SW-PB"))
    )
    (comp (ref "S259")
      (value "MX")
      (footprint "MX-switch - switched pol")
      (description "Switch")
      (libsource (lib "Miscellaneous Devices") (part "SW-PB"))
    )
    (comp (ref "S260")
      (value "MX")
      (footprint "MX-switch - switched pol")
      (description "Switch")
      (libsource (lib "Miscellaneous Devices") (part "SW-PB"))
    )
    (comp (ref "S261")
      (value "MX")
      (footprint "MX-switch - switched pol")
      (description "Switch")
      (libsource (lib "Miscellaneous Devices") (part "SW-PB"))
    )
    (comp (ref "S262")
      (value "MX")
      (footprint "MX-switch - switched pol")
      (description "Switch")
      (libsource (lib "Miscellaneous Devices") (part "SW-PB"))
    )
    (comp (ref "S263")
      (value "MX")
      (footprint "MX-switch - Enter_ANSI_ISO_KEY")
      (description "Switch")
      (libsource (lib "Miscellaneous Devices") (part "SW-PB"))
    )
    (comp (ref "S264")
      (value "MX")
      (footprint "MX-switch - backspace")
      (description "Switch")
      (libsource (lib "Miscellaneous Devices") (part "SW-PB"))
    )
    (comp (ref "S265")
      (value "MX")
      (footprint "MX-switch - 2.25U")
      (description "Switch")
      (libsource (lib "Miscellaneous Devices") (part "SW-PB"))
    )
    (comp (ref "S266")
      (value "MX")
      (footprint "MX-switch - switched pol")
      (description "Switch")
      (libsource (lib "Miscellaneous Devices") (part "SW-PB"))
    )
    (comp (ref "S267")
      (value "MX")
      (footprint "MX-switch - switched pol")
      (description "Switch")
      (libsource (lib "Miscellaneous Devices") (part "SW-PB"))
    )
    (comp (ref "S268")
      (value "MX")
      (footprint "MX-switch - switched pol")
      (description "Switch")
      (libsource (lib "Miscellaneous Devices") (part "SW-PB"))
    )
    (comp (ref "S269")
      (value "MX")
      (footprint "MX-switch - switched pol")
      (description "Switch")
      (libsource (lib "Miscellaneous Devices") (part "SW-PB"))
    )
    (comp (ref "S270")
      (value "MX")
      (footprint "MX-switch - switched pol")
      (description "Switch")
      (libsource (lib "Miscellaneous Devices") (part "SW-PB"))
    )
    (comp (ref "S271")
      (value "MX")
      (footprint "MX-switch - switched pol")
      (description "Switch")
      (libsource (lib "Miscellaneous Devices") (part "SW-PB"))
    )
    (comp (ref "S272")
      (value "MX")
      (footprint "MX-switch - switched pol")
      (description "Switch")
      (libsource (lib "Miscellaneous Devices") (part "SW-PB"))
    )
    (comp (ref "S273")
      (value "MX")
      (footprint "MX-switch - switched pol")
      (description "Switch")
      (libsource (lib "Miscellaneous Devices") (part "SW-PB"))
    )
    (comp (ref "S274")
      (value "MX")
      (footprint "MX-switch - switched pol")
      (description "Switch")
      (libsource (lib "Miscellaneous Devices") (part "SW-PB"))
    )
    (comp (ref "S275")
      (value "MX")
      (footprint "MX-switch - switched pol")
      (description "Switch")
      (libsource (lib "Miscellaneous Devices") (part "SW-PB"))
    )
    (comp (ref "S276")
      (value "MX")
      (footprint "MX-switch - switched pol")
      (description "Switch")
      (libsource (lib "Miscellaneous Devices") (part "SW-PB"))
    )
    (comp (ref "S277")
      (value "MX")
      (footprint "MX-switch - right shift")
      (description "Switch")
      (libsource (lib "Miscellaneous Devices") (part "SW-PB"))
    )
    (comp (ref "S278")
      (value "MX")
      (footprint "MX-switch - switched pol")
      (description "Switch")
      (libsource (lib "Miscellaneous Devices") (part "SW-PB"))
    )
    (comp (ref "S279")
      (value "MX")
      (footprint "MX-switch")
      (description "Switch")
      (libsource (lib "Miscellaneous Devices") (part "SW-PB"))
    )
    (comp (ref "S280")
      (value "MX")
      (footprint "MX-switch - 1.5U - switched pol")
      (description "Switch")
      (libsource (lib "Miscellaneous Devices") (part "SW-PB"))
    )
    (comp (ref "S281")
      (value "MX")
      (footprint "MX-switch")
      (description "Switch")
      (libsource (lib "Miscellaneous Devices") (part "SW-PB"))
    )
    (comp (ref "S282")
      (value "MX")
      (footprint "MX-switch - 1.5U")
      (description "Switch")
      (libsource (lib "Miscellaneous Devices") (part "SW-PB"))
    )
    (comp (ref "S283")
      (value "MX")
      (footprint "MX-switch - 7u space")
      (description "Switch")
      (libsource (lib "Miscellaneous Devices") (part "SW-PB"))
    )
    (comp (ref "S284")
      (value "MX")
      (footprint "MX-switch - 1.5U")
      (description "Switch")
      (libsource (lib "Miscellaneous Devices") (part "SW-PB"))
    )
    (comp (ref "S285")
      (value "MX")
      (footprint "MX-switch")
      (description "Switch")
      (libsource (lib "Miscellaneous Devices") (part "SW-PB"))
    )
    (comp (ref "S286")
      (value "MX")
      (footprint "MX-switch - 1.5U")
      (description "Switch")
      (libsource (lib "Miscellaneous Devices") (part "SW-PB"))
    )
    (comp (ref "S287")
      (value "MX")
      (footprint "MX-switch")
      (description "Switch")
      (libsource (lib "Miscellaneous Devices") (part "SW-PB"))
    )
    (comp (ref "S288")
      (value "MX")
      (footprint "MX-switch")
      (description "Switch")
      (libsource (lib "Miscellaneous Devices") (part "SW-PB"))
    )
    (comp (ref "S289")
      (value "MX")
      (footprint "MX-switch")
      (description "Switch")
      (libsource (lib "Miscellaneous Devices") (part "SW-PB"))
    )
  )
  (nets
    (net (code "1") (name "/col1") (class "Default")
      (node (ref "S201") (pin "2") (pinfunction "2_2") (pintype "passive"))
      (node (ref "S217") (pin "2") (pinfunction "2_2") (pintype "passive"))
      (node (ref "S234") (pin "2") (pinfunction "2_2") (pintype "passive"))
      (node (ref "S251") (pin "2") (pinfunction "2_2") (pintype "passive"))
      (node (ref "S265") (pin "2") (pinfunction "2_2") (pintype "passive"))
      (node (ref "S280") (pin "2") (pinfunction "2_2") (pintype "passive"))
    )
    (net (code "2") (name "/col2") (class "Default")
      (node (ref "S218") (pin "2") (pinfunction "2_2") (pintype "passive"))
      (node (ref "S235") (pin "2") (pinfunction "2_2") (pintype "passive"))
      (node (ref "S252") (pin "2") (pinfunction "2_2") (pintype "passive"))
      (node (ref "S266") (pin "2") (pinfunction "2_2") (pintype "passive"))
    )
    (net (code "3") (name "/col3") (class "Default")
      (node (ref "S202") (pin "2") (pinfunction "2_2") (pintype "passive"))
      (node (ref "S219") (pin "2") (pinfunction "2_2") (pintype "passive"))
      (node (ref "S236") (pin "2") (pinfunction "2_2") (pintype "passive"))
      (node (ref "S253") (pin "2") (pinfunction "2_2") (pintype "passive"))
      (node (ref "S267") (pin "2") (pinfunction "2_2") (pintype "passive"))
      (node (ref "S281") (pin "2") (pinfunction "2_2") (pintype "passive"))
    )
    (net (code "4") (name "/col4") (class "Default")
      (node (ref "S203") (pin "2") (pinfunction "2_2") (pintype "passive"))
      (node (ref "S220") (pin "2") (pinfunction "2_2") (pintype "passive"))
      (node (ref "S237") (pin "2") (pinfunction "2_2") (pintype "passive"))
      (node (ref "S254") (pin "2") (pinfunction "2_2") (pintype "passive"))
      (node (ref "S268") (pin "2") (pinfunction "2_2") (pintype "passive"))
      (node (ref "S282") (pin "2") (pinfunction "2_2") (pintype "passive"))
    )
    (net (code "5") (name "/col5") (class "Default")
      (node (ref "S204") (pin "2") (pinfunction "2_2") (pintype "passive"))
      (node (ref "S221") (pin "2") (pinfunction "2_2") (pintype "passive"))
      (node (ref "S238") (pin "2") (pinfunction "2_2") (pintype "passive"))
      (node (ref "S255") (pin "2") (pinfunction "2_2") (pintype "passive"))
      (node (ref "S269") (pin "2") (pinfunction "2_2") (pintype "passive"))
    )
    (net (code "6") (name "/col6") (class "Default")
      (node (ref "S205") (pin "2") (pinfunction "2_2") (pintype "passive"))
      (node (ref "S222") (pin "2") (pinfunction "2_2") (pintype "passive"))
      (node (ref "S239") (pin "2") (pinfunction "2_2") (pintype "passive"))
      (node (ref "S256") (pin "2") (pinfunction "2_2") (pintype "passive"))
      (node (ref "S270") (pin "2") (pinfunction "2_2") (pintype "passive"))
    )
    (net (code "7") (name "/col7") (class "Default")
      (node (ref "S206") (pin "2") (pinfunction "2_2") (pintype "passive"))
      (node (ref "S223") (pin "2") (pinfunction "2_2") (pintype "passive"))
      (node (ref "S240") (pin "2") (pinfunction "2_2") (pintype "passive"))
      (node (ref "S257") (pin "2") (pinfunction "2_2") (pintype "passive"))
      (node (ref "S271") (pin "2") (pinfunction "2_2") (pintype "passive"))
    )
    (net (code "8") (name "/col8") (class "Default")
      (node (ref "S207") (pin "2") (pinfunction "2_2") (pintype "passive"))
      (node (ref "S224") (pin "2") (pinfunction "2_2") (pintype "passive"))
      (node (ref "S241") (pin "2") (pinfunction "2_2") (pintype "passive"))
      (node (ref "S258") (pin "2") (pinfunction "2_2") (pintype "passive"))
      (node (ref "S272") (pin "2") (pinfunction "2_2") (pintype "passive"))
      (node (ref "S283") (pin "2") (pinfunction "2_2") (pintype "passive"))
    )
    (net (code "9") (name "/col9") (class "Default")
      (node (ref "S208") (pin "2") (pinfunction "2_2") (pintype "passive"))
      (node (ref "S225") (pin "2") (pinfunction "2_2") (pintype "passive"))
      (node (ref "S242") (pin "2") (pinfunction "2_2") (pintype "passive"))
      (node (ref "S259") (pin "2") (pinfunction "2_2") (pintype "passive"))
      (node (ref "S273") (pin "2") (pinfunction "2_2") (pintype "passive"))
    )
    (net (code "10") (name "/col10") (class "Default")
      (node (ref "S209") (pin "2") (pinfunction "2_2") (pintype "passive"))
      (node (ref "S226") (pin "2") (pinfunction "2_2") (pintype "passive"))
      (node (ref "S243") (pin "2") (pinfunction "2_2") (pintype "passive"))
      (node (ref "S260") (pin "2") (pinfunction "2_2") (pintype "passive"))
      (node (ref "S274") (pin "2") (pinfunction "2_2") (pintype "passive"))
    )
    (net (code "11") (name "/col11") (class "Default")
      (node (ref "S210") (pin "2") (pinfunction "2_2") (pintype "passive"))
      (node (ref "S227") (pin "2") (pinfunction "2_2") (pintype "passive"))
      (node (ref "S244") (pin "2") (pinfunction "2_2") (pintype "passive"))
      (node (ref "S261") (pin "2") (pinfunction "2_2") (pintype "passive"))
      (node (ref "S275") (pin "2") (pinfunction "2_2") (pintype "passive"))
    )
    (net (code "12") (name "/col12") (class "Default")
      (node (ref "S211") (pin "2") (pinfunction "2_2") (pintype "passive"))
      (node (ref "S228") (pin "2") (pinfunction "2_2") (pintype "passive"))
      (node (ref "S245") (pin "2") (pinfunction "2_2") (pintype "passive"))
      (node (ref "S262") (pin "2") (pinfunction "2_2") (pintype "passive"))
      (node (ref "S276") (pin "2") (pinfunction "2_2") (pintype "passive"))
      (node (ref "S284") (pin "2") (pinfunction "2_2") (pintype "passive"))
    )
    (net (code "13") (name "/col13") (class "Default")
      (node (ref "S212") (pin "2") (pinfunction "2_2") (pintype "passive"))
      (node (ref "S229") (pin "2") (pinfunction "2_2") (pintype "passive"))
      (node (ref "S246") (pin "2") (pinfunction "2_2") (pintype "passive"))
      (node (ref "S263") (pin "2") (pinfunction "2_2") (pintype "passive"))
      (node (ref "S277") (pin "2") (pinfunction "2_2") (pintype "passive"))
      (node (ref "S285") (pin "2") (pinfunction "2_2") (pintype "passive"))
    )
    (net (code "14") (name "/col14") (class "Default")
      (node (ref "S213") (pin "2") (pinfunction "2_2") (pintype "passive"))
      (node (ref "S230") (pin "2") (pinfunction "2_2") (pintype "passive"))
      (node (ref "S247") (pin "2") (pinfunction "2_2") (pintype "passive"))
      (node (ref "S264") (pin "2") (pinfunction "2_2") (pintype "passive"))
      (node (ref "S278") (pin "2") (pinfunction "2_2") (pintype "passive"))
      (node (ref "S286") (pin "2") (pinfunction "2_2") (pintype "passive"))
    )
    (net (code "15") (name "/col15") (class "Default")
      (node (ref "S214") (pin "2") (pinfunction "2_2") (pintype "passive"))
      (node (ref "S231") (pin "2") (pinfunction "2_2") (pintype "passive"))
      (node (ref "S248") (pin "2") (pinfunction "2_2") (pintype "passive"))
      (node (ref "S287") (pin "2") (pinfunction "2_2") (pintype "passive"))
    )
    (net (code "16") (name "/col16") (class "Default")
      (node (ref "S215") (pin "2") (pinfunction "2_2") (pintype "passive"))
      (node (ref "S232") (pin "2") (pinfunction "2_2") (pintype "passive"))
      (node (ref "S249") (pin "2") (pinfunction "2_2") (pintype "passive"))
      (node (ref "S279") (pin "2") (pinfunction "2_2") (pintype "passive"))
      (node (ref "S288") (pin "2") (pinfunction "2_2") (pintype "passive"))
    )
    (net (code "17") (name "/col17") (class "Default")
      (node (ref "S216") (pin "2") (pinfunction "2_2") (pintype "passive"))
      (node (ref "S233") (pin "2") (pinfunction "2_2") (pintype "passive"))
      (node (ref "S250") (pin "2") (pinfunction "2_2") (pintype "passive"))
      (node (ref "S289") (pin "2") (pinfunction "2_2") (pintype "passive"))
    )
    (net (code "18") (name "/row1") (class "Default")
      (node (ref "D201") (pin "2") (pinfunction "K_2") (pintype "passive"))
      (node (ref "D202") (pin "2") (pinfunction "K_2") (pintype "passive"))
      (node (ref "D203") (pin "2") (pinfunction "K_2") (pintype "passive"))
      (node (ref "D204") (pin "2") (pinfunction "K_2") (pintype "passive"))
      (node (ref "D205") (pin "2") (pinfunction "K_2") (pintype "passive"))
      (node (ref "D206") (pin "2") (pinfunction "K_2") (pintype "passive"))
      (node (ref "D207") (pin "2") (pinfunction "K_2") (pintype "passive"))
      (node (ref "D208") (pin "2") (pinfunction "K_2") (pintype "passive"))
      (node (ref "D209") (pin "2") (pinfunction "K_2") (pintype "passive"))
      (node (ref "D210") (pin "2") (pinfunction "K_2") (pintype "passive"))
      (node (ref "D211") (pin "2") (pinfunction "K_2") (pintype "passive"))
      (node (ref "D212") (pin "2") (pinfunction "K_2") (pintype "passive"))
      (node (ref "D213") (pin "2") (pinfunction "K_2") (pintype "passive"))
      (node (ref "D214") (pin "2") (pinfunction "K_2") (pintype "passive"))
      (node (ref "D215") (pin "2") (pinfunction "K_2") (pintype "passive"))
      (node (ref "D216") (pin "2") (pinfunction "K_2") (pintype "passive"))
    )
    (net (code "19") (name "/row2") (class "Default")
      (node (ref "D217") (pin "2") (pinfunction "K_2") (pintype "passive"))
      (node (ref "D218") (pin "2") (pinfunction "K_2") (pintype "passive"))
      (node (ref "D219") (pin "2") (pinfunction "K_2") (pintype "passive"))
      (node (ref "D220") (pin "2") (pinfunction "K_2") (pintype "passive"))
      (node (ref "D221") (pin "2") (pinfunction "K_2") (pintype "passive"))
      (node (ref "D222") (pin "2") (pinfunction "K_2") (pintype "passive"))
      (node (ref "D223") (pin "2") (pinfunction "K_2") (pintype "passive"))
      (node (ref "D224") (pin "2") (pinfunction "K_2") (pintype "passive"))
      (node (ref "D225") (pin "2") (pinfunction "K_2") (pintype "passive"))
      (node (ref "D226") (pin "2") (pinfunction "K_2") (pintype "passive"))
      (node (ref "D227") (pin "2") (pinfunction "K_2") (pintype "passive"))
      (node (ref "D228") (pin "2") (pinfunction "K_2") (pintype "passive"))
      (node (ref "D229") (pin "2") (pinfunction "K_2") (pintype "passive"))
      (node (ref "D230") (pin "2") (pinfunction "K_2") (pintype "passive"))
      (node (ref "D231") (pin "2") (pinfunction "K_2") (pintype "passive"))
      (node (ref "D232") (pin "2") (pinfunction "K_2") (pintype "passive"))
      (node (ref "D233") (pin "2") (pinfunction "K_2") (pintype "passive"))
    )
    (net (code "20") (name "/row3") (class "Default")
      (node (ref "D234") (pin "2") (pinfunction "K_2") (pintype "passive"))
      (node (ref "D235") (pin "2") (pinfunction "K_2") (pintype "passive"))
      (node (ref "D236") (pin "2") (pinfunction "K_2") (pintype "passive"))
      (node (ref "D237") (pin "2") (pinfunction "K_2") (pintype "passive"))
      (node (ref "D238") (pin "2") (pinfunction "K_2") (pintype "passive"))
      (node (ref "D239") (pin "2") (pinfunction "K_2") (pintype "passive"))
      (node (ref "D240") (pin "2") (pinfunction "K_2") (pintype "passive"))
      (node (ref "D241") (pin "2") (pinfunction "K_2") (pintype "passive"))
      (node (ref "D242") (pin "2") (pinfunction "K_2") (pintype "passive"))
      (node (ref "D243") (pin "2") (pinfunction "K_2") (pintype "passive"))
      (node (ref "D244") (pin "2") (pinfunction "K_2") (pintype "passive"))
      (node (ref "D245") (pin "2") (pinfunction "K_2") (pintype "passive"))
      (node (ref "D246") (pin "2") (pinfunction "K_2") (pintype "passive"))
      (node (ref "D247") (pin "2") (pinfunction "K_2") (pintype "passive"))
      (node (ref "D248") (pin "2") (pinfunction "K_2") (pintype "passive"))
      (node (ref "D249") (pin "2") (pinfunction "K_2") (pintype "passive"))
      (node (ref "D250") (pin "2") (pinfunction "K_2") (pintype "passive"))
    )
    (net (code "21") (name "/row4") (class "Default")
      (node (ref "D251") (pin "2") (pinfunction "K_2") (pintype "passive"))
      (node (ref "D252") (pin "2") (pinfunction "K_2") (pintype "passive"))
      (node (ref "D253") (pin "2") (pinfunction "K_2") (pintype "passive"))
      (node (ref "D254") (pin "2") (pinfunction "K_2") (pintype "passive"))
      (node (ref "D255") (pin "2") (pinfunction "K_2") (pintype "passive"))
      (node (ref "D256") (pin "2") (pinfunction "K_2") (pintype "passive"))
      (node (ref "D257") (pin "2") (pinfunction "K_2") (pintype "passive"))
      (node (ref "D258") (pin "2") (pinfunction "K_2") (pintype "passive"))
      (node (ref "D259") (pin "2") (pinfunction "K_2") (pintype "passive"))
      (node (ref "D260") (pin "2") (pinfunction "K_2") (pintype "passive"))
      (node (ref "D261") (pin "2") (pinfunction "K_2") (pintype "passive"))
      (node (ref "D262") (pin "2") (pinfunction "K_2") (pintype "passive"))
      (node (ref "D263") (pin "2") (pinfunction "K_2") (pintype "passive"))
      (node (ref "D264") (pin "2") (pinfunction "K_2") (pintype "passive"))
    )
    (net (code "22") (name "/row5") (class "Default")
      (node (ref "D265") (pin "2") (pinfunction "K_2") (pintype "passive"))
      (node (ref "D266") (pin "2") (pinfunction "K_2") (pintype "passive"))
      (node (ref "D267") (pin "2") (pinfunction "K_2") (pintype "passive"))
      (node (ref "D268") (pin "2") (pinfunction "K_2") (pintype "passive"))
      (node (ref "D269") (pin "2") (pinfunction "K_2") (pintype "passive"))
      (node (ref "D270") (pin "2") (pinfunction "K_2") (pintype "passive"))
      (node (ref "D271") (pin "2") (pinfunction "K_2") (pintype "passive"))
      (node (ref "D272") (pin "2") (pinfunction "K_2") (pintype "passive"))
      (node (ref "D273") (pin "2") (pinfunction "K_2") (pintype "passive"))
      (node (ref "D274") (pin "2") (pinfunction "K_2") (pintype "passive"))
      (node (ref "D275") (pin "2") (pinfunction "K_2") (pintype "passive"))
      (node (ref "D276") (pin "2") (pinfunction "K_2") (pintype "passive"))
      (node (ref "D277") (pin "2") (pinfunction "K_2") (pintype "passive"))
      (node (ref "D278") (pin "2") (pinfunction "K_2") (pintype "passive"))
      (node (ref "D279") (pin "2") (pinfunction "K_2") (pintype "passive"))
    )
    (net (code "23") (name "/row6") (class "Default")
      (node (ref "D280") (pin "2") (pinfunction "K_2") (pintype "passive"))
      (node (ref "D281") (pin "2") (pinfunction "K_2") (pintype "passive"))
      (node (ref "D282") (pin "2") (pinfunction "K_2") (pintype "passive"))
      (node (ref "D283") (pin "2") (pinfunction "K_2") (pintype "passive"))
      (node (ref "D284") (pin "2") (pinfunction "K_2") (pintype "passive"))
      (node (ref "D285") (pin "2") (pinfunction "K_2") (pintype "passive"))
      (node (ref "D286") (pin "2") (pinfunction "K_2") (pintype "passive"))
      (node (ref "D287") (pin "2") (pinfunction "K_2") (pintype "passive"))
      (node (ref "D288") (pin "2") (pinfunction "K_2") (pintype "passive"))
      (node (ref "D289") (pin "2") (pinfunction "K_2") (pintype "passive"))
    )
    (net (code "24") (name "Net-(D201-A)") (class "Default")
      (node (ref "D201") (pin "1") (pinfunction "A_1") (pintype "passive"))
      (node (ref "S201") (pin "1") (pinfunction "1_1") (pintype "passive"))
    )
    (net (code "25") (name "Net-(D202-A)") (class "Default")
      (node (ref "D202") (pin "1") (pinfunction "A_1") (pintype "passive"))
      (node (ref "S202") (pin "1") (pinfunction "1_1") (pintype "passive"))
    )
    (net (code "26") (name "Net-(D203-A)") (class "Default")
      (node (ref "D203") (pin "1") (pinfunction "A_1") (pintype "passive"))
      (node (ref "S203") (pin "1") (pinfunction "1_1") (pintype "passive"))
    )
    (net (code "27") (name "Net-(D204-A)") (class "Default")
      (node (ref "D204") (pin "1") (pinfunction "A_1") (pintype "passive"))
      (node (ref "S204") (pin "1") (pinfunction "1_1") (pintype "passive"))
    )
    (net (code "28") (name "Net-(D205-A)") (class "Default")
      (node (ref "D205") (pin "1") (pinfunction "A_1") (pintype "passive"))
      (node (ref "S205") (pin "1") (pinfunction "1_1") (pintype "passive"))
    )
    (net (code "29") (name "Net-(D206-A)") (class "Default")
      (node (ref "D206") (pin "1") (pinfunction "A_1") (pintype "passive"))
      (node (ref "S206") (pin "1") (pinfunction "1_1") (pintype "passive"))
    )
    (net (code "30") (name "Net-(D207-A)") (class "Default")
      (node (ref "D207") (pin "1") (pinfunction "A_1") (pintype "passive"))
      (node (ref "S207") (pin "1") (pinfunction "1_1") (pintype "passive"))
    )
    (net (code "31") (name "Net-(D208-A)") (class "Default")
      (node (ref "D208") (pin "1") (pinfunction "A_1") (pintype "passive"))
      (node (ref "S208") (pin "1") (pinfunction "1_1") (pintype "passive"))
    )
    (net (code "32") (name "Net-(D209-A)") (class "Default")
      (node (ref "D209") (pin "1") (pinfunction "A_1") (pintype "passive"))
      (node (ref "S209") (pin "1") (pinfunction "1_1") (pintype "passive"))
    )
    (net (code "33") (name "Net-(D210-A)") (class "Default")
      (node (ref "D210") (pin "1") (pinfunction "A_1") (pintype "passive"))
      (node (ref "S210") (pin "1") (pinfunction "1_1") (pintype "passive"))
    )
    (net (code "34") (name "Net-(D211-A)") (class "Default")
      (node (ref "D211") (pin "1") (pinfunction "A_1") (pintype "passive"))
      (node (ref "S211") (pin "1") (pinfunction "1_1") (pintype "passive"))
    )
    (net (code "35") (name "Net-(D212-A)") (class "Default")
      (node (ref "D212") (pin "1") (pinfunction "A_1") (pintype "passive"))
      (node (ref "S212") (pin "1") (pinfunction "1_1") (pintype "passive"))
    )
    (net (code "36") (name "Net-(D213-A)") (class "Default")
      (node (ref "D213") (pin "1") (pinfunction "A_1") (pintype "passive"))
      (node (ref "S213") (pin "1") (pinfunction "1_1") (pintype "passive"))
    )
    (net (code "37") (name "Net-(D214-A)") (class "Default")
      (node (ref "D214") (pin "1") (pinfunction "A_1") (pintype "passive"))
      (node (ref "S214") (pin "1") (pinfunction "1_1") (pintype "passive"))
    )
    (net (code "38") (name "Net-(D215-A)") (class "Default")
      (node (ref "D215") (pin "1") (pinfunction "A_1") (pintype "passive"))
      (node (ref "S215") (pin "1") (pinfunction "1_1") (pintype "passive"))
    )
    (net (code "39") (name "Net-(D216-A)") (class "Default")
      (node (ref "D216") (pin "1") (pinfunction "A_1") (pintype "passive"))
      (node (ref "S216") (pin "1") (pinfunction "1_1") (pintype "passive"))
    )
    (net (code "40") (name "Net-(D217-A)") (class "Default")
      (node (ref "D217") (pin "1") (pinfunction "A_1") (pintype "passive"))
      (node (ref "S217") (pin "1") (pinfunction "1_1") (pintype "passive"))
    )
    (net (code "41") (name "Net-(D218-A)") (class "Default")
      (node (ref "D218") (pin "1") (pinfunction "A_1") (pintype "passive"))
      (node (ref "S218") (pin "1") (pinfunction "1_1") (pintype "passive"))
    )
    (net (code "42") (name "Net-(D219-A)") (class "Default")
      (node (ref "D219") (pin "1") (pinfunction "A_1") (pintype "passive"))
      (node (ref "S219") (pin "1") (pinfunction "1_1") (pintype "passive"))
    )
    (net (code "43") (name "Net-(D220-A)") (class "Default")
      (node (ref "D220") (pin "1") (pinfunction "A_1") (pintype "passive"))
      (node (ref "S220") (pin "1") (pinfunction "1_1") (pintype "passive"))
    )
    (net (code "44") (name "Net-(D221-A)") (class "Default")
      (node (ref "D221") (pin "1") (pinfunction "A_1") (pintype "passive"))
      (node (ref "S221") (pin "1") (pinfunction "1_1") (pintype "passive"))
    )
    (net (code "45") (name "Net-(D222-A)") (class "Default")
      (node (ref "D222") (pin "1") (pinfunction "A_1") (pintype "passive"))
      (node (ref "S222") (pin "1") (pinfunction "1_1") (pintype "passive"))
    )
    (net (code "46") (name "Net-(D223-A)") (class "Default")
      (node (ref "D223") (pin "1") (pinfunction "A_1") (pintype "passive"))
      (node (ref "S223") (pin "1") (pinfunction "1_1") (pintype "passive"))
    )
    (net (code "47") (name "Net-(D224-A)") (class "Default")
      (node (ref "D224") (pin "1") (pinfunction "A_1") (pintype "passive"))
      (node (ref "S224") (pin "1") (pinfunction "1_1") (pintype "passive"))
    )
    (net (code "48") (name "Net-(D225-A)") (class "Default")
      (node (ref "D225") (pin "1") (pinfunction "A_1") (pintype "passive"))
      (node (ref "S225") (pin "1") (pinfunction "1_1") (pintype "passive"))
    )
    (net (code "49") (name "Net-(D226-A)") (class "Default")
      (node (ref "D226") (pin "1") (pinfunction "A_1") (pintype "passive"))
      (node (ref "S226") (pin "1") (pinfunction "1_1") (pintype "passive"))
    )
    (net (code "50") (name "Net-(D227-A)") (class "Default")
      (node (ref "D227") (pin "1") (pinfunction "A_1") (pintype "passive"))
      (node (ref "S227") (pin "1") (pinfunction "1_1") (pintype "passive"))
    )
    (net (code "51") (name "Net-(D228-A)") (class "Default")
      (node (ref "D228") (pin "1") (pinfunction "A_1") (pintype "passive"))
      (node (ref "S228") (pin "1") (pinfunction "1_1") (pintype "passive"))
    )
    (net (code "52") (name "Net-(D229-A)") (class "Default")
      (node (ref "D229") (pin "1") (pinfunction "A_1") (pintype "passive"))
      (node (ref "S229") (pin "1") (pinfunction "1_1") (pintype "passive"))
    )
    (net (code "53") (name "Net-(D230-A)") (class "Default")
      (node (ref "D230") (pin "1") (pinfunction "A_1") (pintype "passive"))
      (node (ref "S230") (pin "1") (pinfunction "1_1") (pintype "passive"))
    )
    (net (code "54") (name "Net-(D231-A)") (class "Default")
      (node (ref "D231") (pin "1") (pinfunction "A_1") (pintype "passive"))
      (node (ref "S231") (pin "1") (pinfunction "1_1") (pintype "passive"))
    )
    (net (code "55") (name "Net-(D232-A)") (class "Default")
      (node (ref "D232") (pin "1") (pinfunction "A_1") (pintype "passive"))
      (node (ref "S232") (pin "1") (pinfunction "1_1") (pintype "passive"))
    )
    (net (code "56") (name "Net-(D233-A)") (class "Default")
      (node (ref "D233") (pin "1") (pinfunction "A_1") (pintype "passive"))
      (node (ref "S233") (pin "1") (pinfunction "1_1") (pintype "passive"))
    )
    (net (code "57") (name "Net-(D234-A)") (class "Default")
      (node (ref "D234") (pin "1") (pinfunction "A_1") (pintype "passive"))
      (node (ref "S234") (pin "1") (pinfunction "1_1") (pintype "passive"))
    )
    (net (code "58") (name "Net-(D235-A)") (class "Default")
      (node (ref "D235") (pin "1") (pinfunction "A_1") (pintype "passive"))
      (node (ref "S235") (pin "1") (pinfunction "1_1") (pintype "passive"))
    )
    (net (code "59") (name "Net-(D236-A)") (class "Default")
      (node (ref "D236") (pin "1") (pinfunction "A_1") (pintype "passive"))
      (node (ref "S236") (pin "1") (pinfunction "1_1") (pintype "passive"))
    )
    (net (code "60") (name "Net-(D237-A)") (class "Default")
      (node (ref "D237") (pin "1") (pinfunction "A_1") (pintype "passive"))
      (node (ref "S237") (pin "1") (pinfunction "1_1") (pintype "passive"))
    )
    (net (code "61") (name "Net-(D238-A)") (class "Default")
      (node (ref "D238") (pin "1") (pinfunction "A_1") (pintype "passive"))
      (node (ref "S238") (pin "1") (pinfunction "1_1") (pintype "passive"))
    )
    (net (code "62") (name "Net-(D239-A)") (class "Default")
      (node (ref "D239") (pin "1") (pinfunction "A_1") (pintype "passive"))
      (node (ref "S239") (pin "1") (pinfunction "1_1") (pintype "passive"))
    )
    (net (code "63") (name "Net-(D240-A)") (class "Default")
      (node (ref "D240") (pin "1") (pinfunction "A_1") (pintype "passive"))
      (node (ref "S240") (pin "1") (pinfunction "1_1") (pintype "passive"))
    )
    (net (code "64") (name "Net-(D241-A)") (class "Default")
      (node (ref "D241") (pin "1") (pinfunction "A_1") (pintype "passive"))
      (node (ref "S241") (pin "1") (pinfunction "1_1") (pintype "passive"))
    )
    (net (code "65") (name "Net-(D242-A)") (class "Default")
      (node (ref "D242") (pin "1") (pinfunction "A_1") (pintype "passive"))
      (node (ref "S242") (pin "1") (pinfunction "1_1") (pintype "passive"))
    )
    (net (code "66") (name "Net-(D243-A)") (class "Default")
      (node (ref "D243") (pin "1") (pinfunction "A_1") (pintype "passive"))
      (node (ref "S243") (pin "1") (pinfunction "1_1") (pintype "passive"))
    )
    (net (code "67") (name "Net-(D244-A)") (class "Default")
      (node (ref "D244") (pin "1") (pinfunction "A_1") (pintype "passive"))
      (node (ref "S244") (pin "1") (pinfunction "1_1") (pintype "passive"))
    )
    (net (code "68") (name "Net-(D245-A)") (class "Default")
      (node (ref "D245") (pin "1") (pinfunction "A_1") (pintype "passive"))
      (node (ref "S245") (pin "1") (pinfunction "1_1") (pintype "passive"))
    )
    (net (code "69") (name "Net-(D246-A)") (class "Default")
      (node (ref "D246") (pin "1") (pinfunction "A_1") (pintype "passive"))
      (node (ref "S246") (pin "1") (pinfunction "1_1") (pintype "passive"))
    )
    (net (code "70") (name "Net-(D247-A)") (class "Default")
      (node (ref "D247") (pin "1") (pinfunction "A_1") (pintype "passive"))
      (node (ref "S247") (pin "1") (pinfunction "1_1") (pintype "passive"))
    )
    (net (code "71") (name "Net-(D248-A)") (class "Default")
      (node (ref "D248") (pin "1") (pinfunction "A_1") (pintype "passive"))
      (node (ref "S248") (pin "1") (pinfunction "1_1") (pintype "passive"))
    )
    (net (code "72") (name "Net-(D249-A)") (class "Default")
      (node (ref "D249") (pin "1") (pinfunction "A_1") (pintype "passive"))
      (node (ref "S249") (pin "1") (pinfunction "1_1") (pintype "passive"))
    )
    (net (code "73") (name "Net-(D250-A)") (class "Default")
      (node (ref "D250") (pin "1") (pinfunction "A_1") (pintype "passive"))
      (node (ref "S250") (pin "1") (pinfunction "1_1") (pintype "passive"))
    )
    (net (code "74") (name "Net-(D251-A)") (class "Default")
      (node (ref "D251") (pin "1") (pinfunction "A_1") (pintype "passive"))
      (node (ref "S251") (pin "1") (pinfunction "1_1") (pintype "passive"))
    )
    (net (code "75") (name "Net-(D252-A)") (class "Default")
      (node (ref "D252") (pin "1") (pinfunction "A_1") (pintype "passive"))
      (node (ref "S252") (pin "1") (pinfunction "1_1") (pintype "passive"))
    )
    (net (code "76") (name "Net-(D253-A)") (class "Default")
      (node (ref "D253") (pin "1") (pinfunction "A_1") (pintype "passive"))
      (node (ref "S253") (pin "1") (pinfunction "1_1") (pintype "passive"))
    )
    (net (code "77") (name "Net-(D254-A)") (class "Default")
      (node (ref "D254") (pin "1") (pinfunction "A_1") (pintype "passive"))
      (node (ref "S254") (pin "1") (pinfunction "1_1") (pintype "passive"))
    )
    (net (code "78") (name "Net-(D255-A)") (class "Default")
      (node (ref "D255") (pin "1") (pinfunction "A_1") (pintype "passive"))
      (node (ref "S255") (pin "1") (pinfunction "1_1") (pintype "passive"))
    )
    (net (code "79") (name "Net-(D256-A)") (class "Default")
      (node (ref "D256") (pin "1") (pinfunction "A_1") (pintype "passive"))
      (node (ref "S256") (pin "1") (pinfunction "1_1") (pintype "passive"))
    )
    (net (code "80") (name "Net-(D257-A)") (class "Default")
      (node (ref "D257") (pin "1") (pinfunction "A_1") (pintype "passive"))
      (node (ref "S257") (pin "1") (pinfunction "1_1") (pintype "passive"))
    )
    (net (code "81") (name "Net-(D258-A)") (class "Default")
      (node (ref "D258") (pin "1") (pinfunction "A_1") (pintype "passive"))
      (node (ref "S258") (pin "1") (pinfunction "1_1") (pintype "passive"))
    )
    (net (code "82") (name "Net-(D259-A)") (class "Default")
      (node (ref "D259") (pin "1") (pinfunction "A_1") (pintype "passive"))
      (node (ref "S259") (pin "1") (pinfunction "1_1") (pintype "passive"))
    )
    (net (code "83") (name "Net-(D260-A)") (class "Default")
      (node (ref "D260") (pin "1") (pinfunction "A_1") (pintype "passive"))
      (node (ref "S260") (pin "1") (pinfunction "1_1") (pintype "passive"))
    )
    (net (code "84") (name "Net-(D261-A)") (class "Default")
      (node (ref "D261") (pin "1") (pinfunction "A_1") (pintype "passive"))
      (node (ref "S261") (pin "1") (pinfunction "1_1") (pintype "passive"))
    )
    (net (code "85") (name "Net-(D262-A)") (class "Default")
      (node (ref "D262") (pin "1") (pinfunction "A_1") (pintype "passive"))
      (node (ref "S262") (pin "1") (pinfunction "1_1") (pintype "passive"))
    )
    (net (code "86") (name "Net-(D263-A)") (class "Default")
      (node (ref "D263") (pin "1") (pinfunction "A_1") (pintype "passive"))
      (node (ref "S263") (pin "1") (pinfunction "1_1") (pintype "passive"))
    )
    (net (code "87") (name "Net-(D264-A)") (class "Default")
      (node (ref "D264") (pin "1") (pinfunction "A_1") (pintype "passive"))
      (node (ref "S264") (pin "1") (pinfunction "1_1") (pintype "passive"))
    )
    (net (code "88") (name "Net-(D265-A)") (class "Default")
      (node (ref "D265") (pin "1") (pinfunction "A_1") (pintype "passive"))
      (node (ref "S265") (pin "1") (pinfunction "1_1") (pintype "passive"))
    )
    (net (code "89") (name "Net-(D266-A)") (class "Default")
      (node (ref "D266") (pin "1") (pinfunction "A_1") (pintype "passive"))
      (node (ref "S266") (pin "1") (pinfunction "1_1") (pintype "passive"))
    )
    (net (code "90") (name "Net-(D267-A)") (class "Default")
      (node (ref "D267") (pin "1") (pinfunction "A_1") (pintype "passive"))
      (node (ref "S267") (pin "1") (pinfunction "1_1") (pintype "passive"))
    )
    (net (code "91") (name "Net-(D268-A)") (class "Default")
      (node (ref "D268") (pin "1") (pinfunction "A_1") (pintype "passive"))
      (node (ref "S268") (pin "1") (pinfunction "1_1") (pintype "passive"))
    )
    (net (code "92") (name "Net-(D269-A)") (class "Default")
      (node (ref "D269") (pin "1") (pinfunction "A_1") (pintype "passive"))
      (node (ref "S269") (pin "1") (pinfunction "1_1") (pintype "passive"))
    )
    (net (code "93") (name "Net-(D270-A)") (class "Default")
      (node (ref "D270") (pin "1") (pinfunction "A_1") (pintype "passive"))
      (node (ref "S270") (pin "1") (pinfunction "1_1") (pintype "passive"))
    )
    (net (code "94") (name "Net-(D271-A)") (class "Default")
      (node (ref "D271") (pin "1") (pinfunction "A_1") (pintype "passive"))
      (node (ref "S271") (pin "1") (pinfunction "1_1") (pintype "passive"))
    )
    (net (code "95") (name "Net-(D272-A)") (class "Default")
      (node (ref "D272") (pin "1") (pinfunction "A_1") (pintype "passive"))
      (node (ref "S272") (pin "1") (pinfunction "1_1") (pintype "passive"))
    )
    (net (code "96") (name "Net-(D273-A)") (class "Default")
      (node (ref "D273") (pin "1") (pinfunction "A_1") (pintype "passive"))
      (node (ref "S273") (pin "1") (pinfunction "1_1") (pintype "passive"))
    )
    (net (code "97") (name "Net-(D274-A)") (class "Default")
      (node (ref "D274") (pin "1") (pinfunction "A_1") (pintype "passive"))
      (node (ref "S274") (pin "1") (pinfunction "1_1") (pintype "passive"))
    )
    (net (code "98") (name "Net-(D275-A)") (class "Default")
      (node (ref "D275") (pin "1") (pinfunction "A_1") (pintype "passive"))
      (node (ref "S275") (pin "1") (pinfunction "1_1") (pintype "passive"))
    )
    (net (code "99") (name "Net-(D276-A)") (class "Default")
      (node (ref "D276") (pin "1") (pinfunction "A_1") (pintype "passive"))
      (node (ref "S276") (pin "1") (pinfunction "1_1") (pintype "passive"))
    )
    (net (code "100") (name "Net-(D277-A)") (class "Default")
      (node (ref "D277") (pin "1") (pinfunction "A_1") (pintype "passive"))
      (node (ref "S277") (pin "1") (pinfunction "1_1") (pintype "passive"))
    )
    (net (code "101") (name "Net-(D278-A)") (class "Default")
      (node (ref "D278") (pin "1") (pinfunction "A_1") (pintype "passive"))
      (node (ref "S278") (pin "1") (pinfunction "1_1") (pintype "passive"))
    )
    (net (code "102") (name "Net-(D279-A)") (class "Default")
      (node (ref "D279") (pin "1") (pinfunction "A_1") (pintype "passive"))
      (node (ref "S279") (pin "1") (pinfunction "1_1") (pintype "passive"))
    )
    (net (code "103") (name "Net-(D280-A)") (class "Default")
      (node (ref "D280") (pin "1") (pinfunction "A_1") (pintype "passive"))
      (node (ref "S280") (pin "1") (pinfunction "1_1") (pintype "passive"))
    )
    (net (code "104") (name "Net-(D281-A)") (class "Default")
      (node (ref "D281") (pin "1") (pinfunction "A_1") (pintype "passive"))
      (node (ref "S281") (pin "1") (pinfunction "1_1") (pintype "passive"))
    )
    (net (code "105") (name "Net-(D282-A)") (class "Default")
      (node (ref "D282") (pin "1") (pinfunction "A_1") (pintype "passive"))
      (node (ref "S282") (pin "1") (pinfunction "1_1") (pintype "passive"))
    )
    (net (code "106") (name "Net-(D283-A)") (class "Default")
      (node (ref "D283") (pin "1") (pinfunction "A_1") (pintype "passive"))
      (node (ref "S283") (pin "1") (pinfunction "1_1") (pintype "passive"))
    )
    (net (code "107") (name "Net-(D284-A)") (class "Default")
      (node (ref "D284") (pin "1") (pinfunction "A_1") (pintype "passive"))
      (node (ref "S284") (pin "1") (pinfunction "1_1") (pintype "passive"))
    )
    (net (code "108") (name "Net-(D285-A)") (class "Default")
      (node (ref "D285") (pin "1") (pinfunction "A_1") (pintype "passive"))
      (node (ref "S285") (pin "1") (pinfunction "1_1") (pintype "passive"))
    )
    (net (code "109") (name "Net-(D286-A)") (class "Default")
      (node (ref "D286") (pin "1") (pinfunction "A_1") (pintype "passive"))
      (node (ref "S286") (pin "1") (pinfunction "1_1") (pintype "passive"))
    )
    (net (code "110") (name "Net-(D287-A)") (class "Default")
      (node (ref "D287") (pin "1") (pinfunction "A_1") (pintype "passive"))
      (node (ref "S287") (pin "1") (pinfunction "1_1") (pintype "passive"))
    )
    (net (code "111") (name "Net-(D288-A)") (class "Default")
      (node (ref "D288") (pin "1") (pinfunction "A_1") (pintype "passive"))
      (node (ref "S288") (pin "1") (pinfunction "1_1") (pintype "passive"))
    )
    (net (code "112") (name "Net-(D289-A)") (class "Default")
      (node (ref "D289") (pin "1") (pinfunction "A_1") (pintype "passive"))
      (node (ref "S289") (pin "1") (pinfunction "1_1") (pintype "passive"))
    )
  )
)
